# Schemat.net
KiCad netlist of a schematic drawn in EAGLE
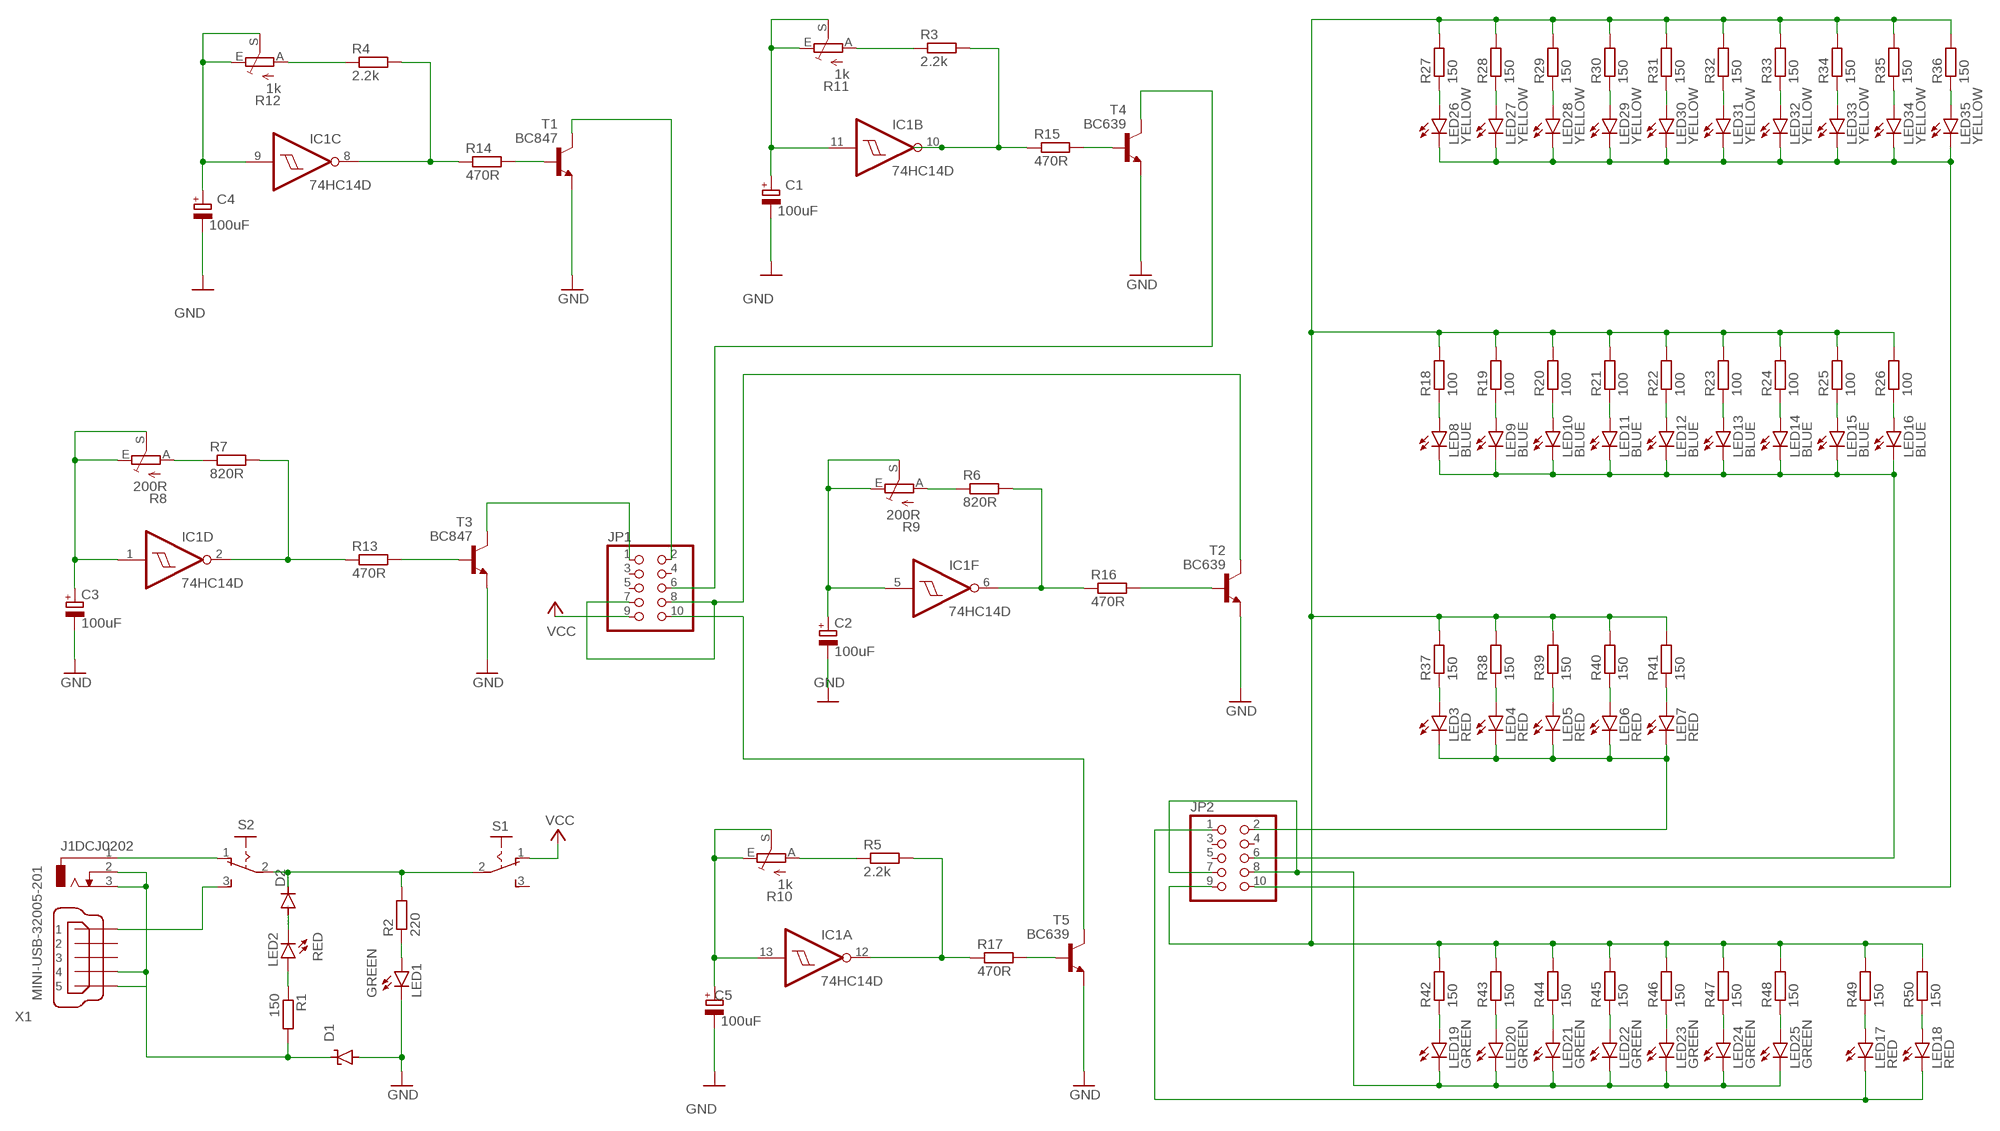
[diagram p0: schematic, sheet 1]

(export (version "E")
  (design (tool "Eeschema 10.0.6"))
  (components
    (comp (ref "C1")
      (value "100uF")
      (footprint "eagle-import:E2,5-6")
      (libsource (lib "eagle-import") (part "CPOL-EUE2.5-6"))
    )
    (comp (ref "C2")
      (value "100uF")
      (footprint "eagle-import:E2,5-6")
      (libsource (lib "eagle-import") (part "CPOL-EUE2.5-6"))
    )
    (comp (ref "C3")
      (value "100uF")
      (footprint "eagle-import:E2,5-6")
      (libsource (lib "eagle-import") (part "CPOL-EUE2.5-6"))
    )
    (comp (ref "C4")
      (value "100uF")
      (footprint "eagle-import:E2,5-6")
      (libsource (lib "eagle-import") (part "CPOL-EUE2.5-6"))
    )
    (comp (ref "C5")
      (value "100uF")
      (footprint "eagle-import:E2,5-6")
      (libsource (lib "eagle-import") (part "CPOL-EUE2.5-6"))
    )
    (comp (ref "D1")
      (value "SUPPRESSOR-SMBJ")
      (footprint "eagle-import:SMBJ")
      (libsource (lib "eagle-import") (part "SUPPRESSOR-SMBJ"))
    )
    (comp (ref "D2")
      (value "DIODE-DO214AC")
      (footprint "eagle-import:DO214AC")
      (libsource (lib "eagle-import") (part "DIODE-DO214AC"))
    )
    (comp (ref "IC1")
      (value "74HC14D")
      (footprint "eagle-import:SO14")
      (libsource (lib "eagle-import") (part "7414DHC"))
    )
    (comp (ref "J1")
      (value "DCJ0202")
      (footprint "eagle-import:DCJ0202")
      (libsource (lib "eagle-import") (part "DCJ0202"))
    )
    (comp (ref "JP1")
      (value "PINHD-2X5")
      (footprint "eagle-import:2X05")
      (libsource (lib "eagle-import") (part "PINHD-2X5"))
    )
    (comp (ref "JP2")
      (value "PINHD-2X5/90")
      (footprint "eagle-import:2X05_90")
      (libsource (lib "eagle-import") (part "PINHD-2X5/90"))
    )
    (comp (ref "LED1")
      (value "GREEN")
      (footprint "eagle-import:LED3MM")
      (libsource (lib "eagle-import") (part "LED3MM"))
    )
    (comp (ref "LED2")
      (value "RED")
      (footprint "eagle-import:LED5MM")
      (libsource (lib "eagle-import") (part "LED5MM"))
    )
    (comp (ref "LED3")
      (value "RED")
      (footprint "eagle-import:LED5MM")
      (libsource (lib "eagle-import") (part "LED5MM"))
    )
    (comp (ref "LED4")
      (value "RED")
      (footprint "eagle-import:LED5MM")
      (libsource (lib "eagle-import") (part "LED5MM"))
    )
    (comp (ref "LED5")
      (value "RED")
      (footprint "eagle-import:LED5MM")
      (libsource (lib "eagle-import") (part "LED5MM"))
    )
    (comp (ref "LED6")
      (value "RED")
      (footprint "eagle-import:LED5MM")
      (libsource (lib "eagle-import") (part "LED5MM"))
    )
    (comp (ref "LED7")
      (value "RED")
      (footprint "eagle-import:LED5MM")
      (libsource (lib "eagle-import") (part "LED5MM"))
    )
    (comp (ref "LED8")
      (value "BLUE")
      (footprint "eagle-import:LED5MM")
      (libsource (lib "eagle-import") (part "LED5MM"))
    )
    (comp (ref "LED9")
      (value "BLUE")
      (footprint "eagle-import:LED5MM")
      (libsource (lib "eagle-import") (part "LED5MM"))
    )
    (comp (ref "LED10")
      (value "BLUE")
      (footprint "eagle-import:LED5MM")
      (libsource (lib "eagle-import") (part "LED5MM"))
    )
    (comp (ref "LED11")
      (value "BLUE")
      (footprint "eagle-import:LED5MM")
      (libsource (lib "eagle-import") (part "LED5MM"))
    )
    (comp (ref "LED12")
      (value "BLUE")
      (footprint "eagle-import:LED5MM")
      (libsource (lib "eagle-import") (part "LED5MM"))
    )
    (comp (ref "LED13")
      (value "BLUE")
      (footprint "eagle-import:LED5MM")
      (libsource (lib "eagle-import") (part "LED5MM"))
    )
    (comp (ref "LED14")
      (value "BLUE")
      (footprint "eagle-import:LED5MM")
      (libsource (lib "eagle-import") (part "LED5MM"))
    )
    (comp (ref "LED15")
      (value "BLUE")
      (footprint "eagle-import:LED5MM")
      (libsource (lib "eagle-import") (part "LED5MM"))
    )
    (comp (ref "LED16")
      (value "BLUE")
      (footprint "eagle-import:LED5MM")
      (libsource (lib "eagle-import") (part "LED5MM"))
    )
    (comp (ref "LED17")
      (value "RED")
      (footprint "eagle-import:LED5MM")
      (libsource (lib "eagle-import") (part "LED5MM"))
    )
    (comp (ref "LED18")
      (value "RED")
      (footprint "eagle-import:LED5MM")
      (libsource (lib "eagle-import") (part "LED5MM"))
    )
    (comp (ref "LED19")
      (value "GREEN")
      (footprint "eagle-import:LED3MM")
      (libsource (lib "eagle-import") (part "LED3MM"))
    )
    (comp (ref "LED20")
      (value "GREEN")
      (footprint "eagle-import:LED3MM")
      (libsource (lib "eagle-import") (part "LED3MM"))
    )
    (comp (ref "LED21")
      (value "GREEN")
      (footprint "eagle-import:LED3MM")
      (libsource (lib "eagle-import") (part "LED3MM"))
    )
    (comp (ref "LED22")
      (value "GREEN")
      (footprint "eagle-import:LED3MM")
      (libsource (lib "eagle-import") (part "LED3MM"))
    )
    (comp (ref "LED23")
      (value "GREEN")
      (footprint "eagle-import:LED3MM")
      (libsource (lib "eagle-import") (part "LED3MM"))
    )
    (comp (ref "LED24")
      (value "GREEN")
      (footprint "eagle-import:LED3MM")
      (libsource (lib "eagle-import") (part "LED3MM"))
    )
    (comp (ref "LED25")
      (value "GREEN")
      (footprint "eagle-import:LED3MM")
      (libsource (lib "eagle-import") (part "LED3MM"))
    )
    (comp (ref "LED26")
      (value "YELLOW")
      (footprint "eagle-import:LED5MM")
      (libsource (lib "eagle-import") (part "LED5MM"))
    )
    (comp (ref "LED27")
      (value "YELLOW")
      (footprint "eagle-import:LED5MM")
      (libsource (lib "eagle-import") (part "LED5MM"))
    )
    (comp (ref "LED28")
      (value "YELLOW")
      (footprint "eagle-import:LED5MM")
      (libsource (lib "eagle-import") (part "LED5MM"))
    )
    (comp (ref "LED29")
      (value "YELLOW")
      (footprint "eagle-import:LED5MM")
      (libsource (lib "eagle-import") (part "LED5MM"))
    )
    (comp (ref "LED30")
      (value "YELLOW")
      (footprint "eagle-import:LED5MM")
      (libsource (lib "eagle-import") (part "LED5MM"))
    )
    (comp (ref "LED31")
      (value "YELLOW")
      (footprint "eagle-import:LED5MM")
      (libsource (lib "eagle-import") (part "LED5MM"))
    )
    (comp (ref "LED32")
      (value "YELLOW")
      (footprint "eagle-import:LED5MM")
      (libsource (lib "eagle-import") (part "LED5MM"))
    )
    (comp (ref "LED33")
      (value "YELLOW")
      (footprint "eagle-import:LED5MM")
      (libsource (lib "eagle-import") (part "LED5MM"))
    )
    (comp (ref "LED34")
      (value "YELLOW")
      (footprint "eagle-import:LED5MM")
      (libsource (lib "eagle-import") (part "LED5MM"))
    )
    (comp (ref "LED35")
      (value "YELLOW")
      (footprint "eagle-import:LED5MM")
      (libsource (lib "eagle-import") (part "LED5MM"))
    )
    (comp (ref "R1")
      (value "150")
      (footprint "eagle-import:R0805")
      (libsource (lib "eagle-import") (part "R-EU_R0805"))
    )
    (comp (ref "R2")
      (value "220")
      (footprint "eagle-import:R0805")
      (libsource (lib "eagle-import") (part "R-EU_R0805"))
    )
    (comp (ref "R3")
      (value "2.2k")
      (footprint "eagle-import:R1206")
      (libsource (lib "eagle-import") (part "R-EU_R1206"))
    )
    (comp (ref "R4")
      (value "2.2k")
      (footprint "eagle-import:R1206")
      (libsource (lib "eagle-import") (part "R-EU_R1206"))
    )
    (comp (ref "R5")
      (value "2.2k")
      (footprint "eagle-import:R1206")
      (libsource (lib "eagle-import") (part "R-EU_R1206"))
    )
    (comp (ref "R6")
      (value "820R")
      (footprint "eagle-import:R1206")
      (libsource (lib "eagle-import") (part "R-EU_R1206"))
    )
    (comp (ref "R7")
      (value "820R")
      (footprint "eagle-import:R1206")
      (libsource (lib "eagle-import") (part "R-EU_R1206"))
    )
    (comp (ref "R8")
      (value "200R")
      (footprint "eagle-import:CA6V")
      (libsource (lib "eagle-import") (part "TRIM_EU-CA6V"))
    )
    (comp (ref "R9")
      (value "200R")
      (footprint "eagle-import:CA6V")
      (libsource (lib "eagle-import") (part "TRIM_EU-CA6V"))
    )
    (comp (ref "R10")
      (value "1k")
      (footprint "eagle-import:CA6V")
      (libsource (lib "eagle-import") (part "TRIM_EU-CA6V"))
    )
    (comp (ref "R11")
      (value "1k")
      (footprint "eagle-import:CA6V")
      (libsource (lib "eagle-import") (part "TRIM_EU-CA6V"))
    )
    (comp (ref "R12")
      (value "1k")
      (footprint "eagle-import:CA6V")
      (libsource (lib "eagle-import") (part "TRIM_EU-CA6V"))
    )
    (comp (ref "R13")
      (value "470R")
      (footprint "eagle-import:R1206")
      (libsource (lib "eagle-import") (part "R-EU_R1206"))
    )
    (comp (ref "R14")
      (value "470R")
      (footprint "eagle-import:R1206")
      (libsource (lib "eagle-import") (part "R-EU_R1206"))
    )
    (comp (ref "R15")
      (value "470R")
      (footprint "eagle-import:R1206")
      (libsource (lib "eagle-import") (part "R-EU_R1206"))
    )
    (comp (ref "R16")
      (value "470R")
      (footprint "eagle-import:R1206")
      (libsource (lib "eagle-import") (part "R-EU_R1206"))
    )
    (comp (ref "R17")
      (value "470R")
      (footprint "eagle-import:R1206")
      (libsource (lib "eagle-import") (part "R-EU_R1206"))
    )
    (comp (ref "R18")
      (value "100")
      (footprint "eagle-import:R0805")
      (libsource (lib "eagle-import") (part "R-EU_R0805"))
    )
    (comp (ref "R19")
      (value "100")
      (footprint "eagle-import:R0805")
      (libsource (lib "eagle-import") (part "R-EU_R0805"))
    )
    (comp (ref "R20")
      (value "100")
      (footprint "eagle-import:R0805")
      (libsource (lib "eagle-import") (part "R-EU_R0805"))
    )
    (comp (ref "R21")
      (value "100")
      (footprint "eagle-import:R0805")
      (libsource (lib "eagle-import") (part "R-EU_R0805"))
    )
    (comp (ref "R22")
      (value "100")
      (footprint "eagle-import:R0805")
      (libsource (lib "eagle-import") (part "R-EU_R0805"))
    )
    (comp (ref "R23")
      (value "100")
      (footprint "eagle-import:R0805")
      (libsource (lib "eagle-import") (part "R-EU_R0805"))
    )
    (comp (ref "R24")
      (value "100")
      (footprint "eagle-import:R0805")
      (libsource (lib "eagle-import") (part "R-EU_R0805"))
    )
    (comp (ref "R25")
      (value "100")
      (footprint "eagle-import:R0805")
      (libsource (lib "eagle-import") (part "R-EU_R0805"))
    )
    (comp (ref "R26")
      (value "100")
      (footprint "eagle-import:R0805")
      (libsource (lib "eagle-import") (part "R-EU_R0805"))
    )
    (comp (ref "R27")
      (value "150")
      (footprint "eagle-import:R0805")
      (libsource (lib "eagle-import") (part "R-EU_R0805"))
    )
    (comp (ref "R28")
      (value "150")
      (footprint "eagle-import:R0805")
      (libsource (lib "eagle-import") (part "R-EU_R0805"))
    )
    (comp (ref "R29")
      (value "150")
      (footprint "eagle-import:R0805")
      (libsource (lib "eagle-import") (part "R-EU_R0805"))
    )
    (comp (ref "R30")
      (value "150")
      (footprint "eagle-import:R0805")
      (libsource (lib "eagle-import") (part "R-EU_R0805"))
    )
    (comp (ref "R31")
      (value "150")
      (footprint "eagle-import:R0805")
      (libsource (lib "eagle-import") (part "R-EU_R0805"))
    )
    (comp (ref "R32")
      (value "150")
      (footprint "eagle-import:R0805")
      (libsource (lib "eagle-import") (part "R-EU_R0805"))
    )
    (comp (ref "R33")
      (value "150")
      (footprint "eagle-import:R0805")
      (libsource (lib "eagle-import") (part "R-EU_R0805"))
    )
    (comp (ref "R34")
      (value "150")
      (footprint "eagle-import:R0805")
      (libsource (lib "eagle-import") (part "R-EU_R0805"))
    )
    (comp (ref "R35")
      (value "150")
      (footprint "eagle-import:R0805")
      (libsource (lib "eagle-import") (part "R-EU_R0805"))
    )
    (comp (ref "R36")
      (value "150")
      (footprint "eagle-import:R0805")
      (libsource (lib "eagle-import") (part "R-EU_R0805"))
    )
    (comp (ref "R37")
      (value "150")
      (footprint "eagle-import:R0805")
      (libsource (lib "eagle-import") (part "R-EU_R0805"))
    )
    (comp (ref "R38")
      (value "150")
      (footprint "eagle-import:R0805")
      (libsource (lib "eagle-import") (part "R-EU_R0805"))
    )
    (comp (ref "R39")
      (value "150")
      (footprint "eagle-import:R0805")
      (libsource (lib "eagle-import") (part "R-EU_R0805"))
    )
    (comp (ref "R40")
      (value "150")
      (footprint "eagle-import:R0805")
      (libsource (lib "eagle-import") (part "R-EU_R0805"))
    )
    (comp (ref "R41")
      (value "150")
      (footprint "eagle-import:R0805")
      (libsource (lib "eagle-import") (part "R-EU_R0805"))
    )
    (comp (ref "R42")
      (value "150")
      (footprint "eagle-import:R0805")
      (libsource (lib "eagle-import") (part "R-EU_R0805"))
    )
    (comp (ref "R43")
      (value "150")
      (footprint "eagle-import:R0805")
      (libsource (lib "eagle-import") (part "R-EU_R0805"))
    )
    (comp (ref "R44")
      (value "150")
      (footprint "eagle-import:R0805")
      (libsource (lib "eagle-import") (part "R-EU_R0805"))
    )
    (comp (ref "R45")
      (value "150")
      (footprint "eagle-import:R0805")
      (libsource (lib "eagle-import") (part "R-EU_R0805"))
    )
    (comp (ref "R46")
      (value "150")
      (footprint "eagle-import:R0805")
      (libsource (lib "eagle-import") (part "R-EU_R0805"))
    )
    (comp (ref "R47")
      (value "150")
      (footprint "eagle-import:R0805")
      (libsource (lib "eagle-import") (part "R-EU_R0805"))
    )
    (comp (ref "R48")
      (value "150")
      (footprint "eagle-import:R0805")
      (libsource (lib "eagle-import") (part "R-EU_R0805"))
    )
    (comp (ref "R49")
      (value "150")
      (footprint "eagle-import:R0805")
      (libsource (lib "eagle-import") (part "R-EU_R0805"))
    )
    (comp (ref "R50")
      (value "150")
      (footprint "eagle-import:R0805")
      (libsource (lib "eagle-import") (part "R-EU_R0805"))
    )
    (comp (ref "S1")
      (value "M251")
      (footprint "eagle-import:M251")
      (libsource (lib "eagle-import") (part "M251"))
    )
    (comp (ref "S2")
      (value "M251")
      (footprint "eagle-import:M251")
      (libsource (lib "eagle-import") (part "M251"))
    )
    (comp (ref "T1")
      (value "BC847")
      (footprint "eagle-import:SOT23")
      (libsource (lib "eagle-import") (part "BC847"))
    )
    (comp (ref "T2")
      (value "BC639")
      (footprint "eagle-import:TO92-ECB")
      (libsource (lib "eagle-import") (part "-NPN-TO92-ECBBC639"))
    )
    (comp (ref "T3")
      (value "BC847")
      (footprint "eagle-import:SOT23")
      (libsource (lib "eagle-import") (part "BC847"))
    )
    (comp (ref "T4")
      (value "BC639")
      (footprint "eagle-import:TO92-ECB")
      (libsource (lib "eagle-import") (part "-NPN-TO92-ECBBC639"))
    )
    (comp (ref "T5")
      (value "BC639")
      (footprint "eagle-import:TO92-ECB")
      (libsource (lib "eagle-import") (part "-NPN-TO92-ECBBC639"))
    )
    (comp (ref "X1")
      (value "MINI-USB-32005-201")
      (footprint "eagle-import:32005-201")
      (libsource (lib "eagle-import") (part "MINI-USB-32005-201"))
    )
  )
  (nets
    (net (code "1") (name "GND") (class "Default")
      (node (ref "C1") (pin "-") (pinfunction "-_-") (pintype "passive"))
      (node (ref "C2") (pin "-") (pinfunction "-_-") (pintype "passive"))
      (node (ref "C3") (pin "-") (pinfunction "-_-") (pintype "passive"))
      (node (ref "C4") (pin "-") (pinfunction "-_-") (pintype "passive"))
      (node (ref "C5") (pin "-") (pinfunction "-_-") (pintype "passive"))
      (node (ref "D1") (pin "A") (pinfunction "A_A") (pintype "passive"))
      (node (ref "LED1") (pin "K") (pinfunction "C_K") (pintype "passive"))
      (node (ref "T1") (pin "2") (pinfunction "E_2") (pintype "passive"))
      (node (ref "T2") (pin "E") (pinfunction "E_E") (pintype "passive"))
      (node (ref "T3") (pin "2") (pinfunction "E_2") (pintype "passive"))
      (node (ref "T4") (pin "E") (pinfunction "E_E") (pintype "passive"))
      (node (ref "T5") (pin "E") (pinfunction "E_E") (pintype "passive"))
    )
    (net (code "2") (name "Net-(D1-PadC)") (class "Default")
      (node (ref "D1") (pin "C") (pinfunction "C_C") (pintype "passive"))
      (node (ref "J1") (pin "2") (pinfunction "2_2") (pintype "passive"))
      (node (ref "J1") (pin "3") (pinfunction "3_3") (pintype "passive"))
      (node (ref "R1") (pin "2") (pinfunction "2_2") (pintype "passive"))
      (node (ref "X1") (pin "4") (pinfunction "4_4") (pintype "passive"))
      (node (ref "X1") (pin "5") (pinfunction "5_5") (pintype "passive"))
    )
    (net (code "3") (name "Net-(IC1A-I)") (class "Default")
      (node (ref "C5") (pin "+") (pinfunction "+_+") (pintype "passive"))
      (node (ref "IC1") (pin "13") (pinfunction "I_13") (pintype "input"))
      (node (ref "R10") (pin "E") (pinfunction "E_E") (pintype "passive"))
      (node (ref "R10") (pin "S") (pinfunction "S_S") (pintype "passive"))
    )
    (net (code "4") (name "Net-(IC1A-O)") (class "Default")
      (node (ref "IC1") (pin "12") (pinfunction "O_12") (pintype "output"))
      (node (ref "R17") (pin "1") (pinfunction "1_1") (pintype "passive"))
      (node (ref "R5") (pin "2") (pinfunction "2_2") (pintype "passive"))
    )
    (net (code "5") (name "Net-(IC1B-I)") (class "Default")
      (node (ref "C1") (pin "+") (pinfunction "+_+") (pintype "passive"))
      (node (ref "IC1") (pin "11") (pinfunction "I_11") (pintype "input"))
      (node (ref "R11") (pin "E") (pinfunction "E_E") (pintype "passive"))
      (node (ref "R11") (pin "S") (pinfunction "S_S") (pintype "passive"))
    )
    (net (code "6") (name "Net-(IC1B-O)") (class "Default")
      (node (ref "IC1") (pin "10") (pinfunction "O_10") (pintype "output"))
      (node (ref "R15") (pin "1") (pinfunction "1_1") (pintype "passive"))
      (node (ref "R3") (pin "2") (pinfunction "2_2") (pintype "passive"))
    )
    (net (code "7") (name "Net-(IC1C-I)") (class "Default")
      (node (ref "C4") (pin "+") (pinfunction "+_+") (pintype "passive"))
      (node (ref "IC1") (pin "9") (pinfunction "I_9") (pintype "input"))
      (node (ref "R12") (pin "E") (pinfunction "E_E") (pintype "passive"))
      (node (ref "R12") (pin "S") (pinfunction "S_S") (pintype "passive"))
    )
    (net (code "8") (name "Net-(IC1C-O)") (class "Default")
      (node (ref "IC1") (pin "8") (pinfunction "O_8") (pintype "output"))
      (node (ref "R14") (pin "1") (pinfunction "1_1") (pintype "passive"))
      (node (ref "R4") (pin "2") (pinfunction "2_2") (pintype "passive"))
    )
    (net (code "9") (name "Net-(IC1D-I)") (class "Default")
      (node (ref "C3") (pin "+") (pinfunction "+_+") (pintype "passive"))
      (node (ref "IC1") (pin "1") (pinfunction "I_1") (pintype "input"))
      (node (ref "R8") (pin "E") (pinfunction "E_E") (pintype "passive"))
      (node (ref "R8") (pin "S") (pinfunction "S_S") (pintype "passive"))
    )
    (net (code "10") (name "Net-(IC1D-O)") (class "Default")
      (node (ref "IC1") (pin "2") (pinfunction "O_2") (pintype "output"))
      (node (ref "R13") (pin "1") (pinfunction "1_1") (pintype "passive"))
      (node (ref "R7") (pin "2") (pinfunction "2_2") (pintype "passive"))
    )
    (net (code "11") (name "Net-(IC1F-I)") (class "Default")
      (node (ref "C2") (pin "+") (pinfunction "+_+") (pintype "passive"))
      (node (ref "IC1") (pin "5") (pinfunction "I_5") (pintype "input"))
      (node (ref "R9") (pin "E") (pinfunction "E_E") (pintype "passive"))
      (node (ref "R9") (pin "S") (pinfunction "S_S") (pintype "passive"))
    )
    (net (code "12") (name "Net-(IC1F-O)") (class "Default")
      (node (ref "IC1") (pin "6") (pinfunction "O_6") (pintype "output"))
      (node (ref "R16") (pin "1") (pinfunction "1_1") (pintype "passive"))
      (node (ref "R6") (pin "2") (pinfunction "2_2") (pintype "passive"))
    )
    (net (code "13") (name "Net-(JP1-Pad6)") (class "Default")
      (node (ref "JP1") (pin "6") (pinfunction "6_6") (pintype "passive"))
      (node (ref "T4") (pin "C") (pinfunction "C_C") (pintype "passive"))
    )
    (net (code "14") (name "Net-(JP1-Pad7)") (class "Default")
      (node (ref "JP1") (pin "7") (pinfunction "7_7") (pintype "passive"))
      (node (ref "JP1") (pin "8") (pinfunction "8_8") (pintype "passive"))
      (node (ref "T2") (pin "C") (pinfunction "C_C") (pintype "passive"))
    )
    (net (code "15") (name "Net-(JP1-Pad10)") (class "Default")
      (node (ref "JP1") (pin "10") (pinfunction "10_10") (pintype "passive"))
      (node (ref "T5") (pin "C") (pinfunction "C_C") (pintype "passive"))
    )
    (net (code "16") (name "Net-(JP2-Pad9)") (class "Default")
      (node (ref "JP2") (pin "9") (pinfunction "9_9") (pintype "passive"))
      (node (ref "R18") (pin "2") (pinfunction "2_2") (pintype "passive"))
      (node (ref "R19") (pin "2") (pinfunction "2_2") (pintype "passive"))
      (node (ref "R20") (pin "2") (pinfunction "2_2") (pintype "passive"))
      (node (ref "R21") (pin "2") (pinfunction "2_2") (pintype "passive"))
      (node (ref "R22") (pin "2") (pinfunction "2_2") (pintype "passive"))
      (node (ref "R23") (pin "2") (pinfunction "2_2") (pintype "passive"))
      (node (ref "R24") (pin "2") (pinfunction "2_2") (pintype "passive"))
      (node (ref "R25") (pin "2") (pinfunction "2_2") (pintype "passive"))
      (node (ref "R26") (pin "2") (pinfunction "2_2") (pintype "passive"))
      (node (ref "R27") (pin "2") (pinfunction "2_2") (pintype "passive"))
      (node (ref "R28") (pin "2") (pinfunction "2_2") (pintype "passive"))
      (node (ref "R29") (pin "2") (pinfunction "2_2") (pintype "passive"))
      (node (ref "R30") (pin "2") (pinfunction "2_2") (pintype "passive"))
      (node (ref "R31") (pin "2") (pinfunction "2_2") (pintype "passive"))
      (node (ref "R32") (pin "2") (pinfunction "2_2") (pintype "passive"))
      (node (ref "R33") (pin "2") (pinfunction "2_2") (pintype "passive"))
      (node (ref "R34") (pin "2") (pinfunction "2_2") (pintype "passive"))
      (node (ref "R35") (pin "2") (pinfunction "2_2") (pintype "passive"))
      (node (ref "R36") (pin "2") (pinfunction "2_2") (pintype "passive"))
      (node (ref "R37") (pin "2") (pinfunction "2_2") (pintype "passive"))
      (node (ref "R38") (pin "2") (pinfunction "2_2") (pintype "passive"))
      (node (ref "R39") (pin "2") (pinfunction "2_2") (pintype "passive"))
      (node (ref "R40") (pin "2") (pinfunction "2_2") (pintype "passive"))
      (node (ref "R41") (pin "2") (pinfunction "2_2") (pintype "passive"))
      (node (ref "R42") (pin "2") (pinfunction "2_2") (pintype "passive"))
      (node (ref "R43") (pin "2") (pinfunction "2_2") (pintype "passive"))
      (node (ref "R44") (pin "2") (pinfunction "2_2") (pintype "passive"))
      (node (ref "R45") (pin "2") (pinfunction "2_2") (pintype "passive"))
      (node (ref "R46") (pin "2") (pinfunction "2_2") (pintype "passive"))
      (node (ref "R47") (pin "2") (pinfunction "2_2") (pintype "passive"))
      (node (ref "R48") (pin "2") (pinfunction "2_2") (pintype "passive"))
      (node (ref "R49") (pin "2") (pinfunction "2_2") (pintype "passive"))
      (node (ref "R50") (pin "2") (pinfunction "2_2") (pintype "passive"))
    )
    (net (code "17") (name "Net-(LED1-PadA)") (class "Default")
      (node (ref "LED1") (pin "A") (pinfunction "A_A") (pintype "passive"))
      (node (ref "R2") (pin "1") (pinfunction "1_1") (pintype "passive"))
    )
    (net (code "18") (name "Net-(LED2-C)") (class "Default")
      (node (ref "D2") (pin "A") (pinfunction "A_A") (pintype "passive"))
      (node (ref "LED2") (pin "K") (pinfunction "C_K") (pintype "passive"))
    )
    (net (code "19") (name "Net-(LED2-PadA)") (class "Default")
      (node (ref "LED2") (pin "A") (pinfunction "A_A") (pintype "passive"))
      (node (ref "R1") (pin "1") (pinfunction "1_1") (pintype "passive"))
    )
    (net (code "20") (name "Net-(LED3-C)") (class "Default")
      (node (ref "JP2") (pin "2") (pinfunction "2_2") (pintype "passive"))
      (node (ref "LED3") (pin "K") (pinfunction "C_K") (pintype "passive"))
      (node (ref "LED4") (pin "K") (pinfunction "C_K") (pintype "passive"))
      (node (ref "LED5") (pin "K") (pinfunction "C_K") (pintype "passive"))
      (node (ref "LED6") (pin "K") (pinfunction "C_K") (pintype "passive"))
      (node (ref "LED7") (pin "K") (pinfunction "C_K") (pintype "passive"))
    )
    (net (code "21") (name "Net-(LED3-PadA)") (class "Default")
      (node (ref "LED3") (pin "A") (pinfunction "A_A") (pintype "passive"))
      (node (ref "R37") (pin "1") (pinfunction "1_1") (pintype "passive"))
    )
    (net (code "22") (name "Net-(LED4-PadA)") (class "Default")
      (node (ref "LED4") (pin "A") (pinfunction "A_A") (pintype "passive"))
      (node (ref "R38") (pin "1") (pinfunction "1_1") (pintype "passive"))
    )
    (net (code "23") (name "Net-(LED5-PadA)") (class "Default")
      (node (ref "LED5") (pin "A") (pinfunction "A_A") (pintype "passive"))
      (node (ref "R39") (pin "1") (pinfunction "1_1") (pintype "passive"))
    )
    (net (code "24") (name "Net-(LED6-PadA)") (class "Default")
      (node (ref "LED6") (pin "A") (pinfunction "A_A") (pintype "passive"))
      (node (ref "R40") (pin "1") (pinfunction "1_1") (pintype "passive"))
    )
    (net (code "25") (name "Net-(LED7-PadA)") (class "Default")
      (node (ref "LED7") (pin "A") (pinfunction "A_A") (pintype "passive"))
      (node (ref "R41") (pin "1") (pinfunction "1_1") (pintype "passive"))
    )
    (net (code "26") (name "Net-(LED8-PadA)") (class "Default")
      (node (ref "LED8") (pin "A") (pinfunction "A_A") (pintype "passive"))
      (node (ref "R18") (pin "1") (pinfunction "1_1") (pintype "passive"))
    )
    (net (code "27") (name "Net-(LED9-PadA)") (class "Default")
      (node (ref "LED9") (pin "A") (pinfunction "A_A") (pintype "passive"))
      (node (ref "R19") (pin "1") (pinfunction "1_1") (pintype "passive"))
    )
    (net (code "28") (name "Net-(LED10-C)") (class "Default")
      (node (ref "JP2") (pin "6") (pinfunction "6_6") (pintype "passive"))
      (node (ref "LED10") (pin "K") (pinfunction "C_K") (pintype "passive"))
      (node (ref "LED11") (pin "K") (pinfunction "C_K") (pintype "passive"))
      (node (ref "LED12") (pin "K") (pinfunction "C_K") (pintype "passive"))
      (node (ref "LED13") (pin "K") (pinfunction "C_K") (pintype "passive"))
      (node (ref "LED14") (pin "K") (pinfunction "C_K") (pintype "passive"))
      (node (ref "LED15") (pin "K") (pinfunction "C_K") (pintype "passive"))
      (node (ref "LED16") (pin "K") (pinfunction "C_K") (pintype "passive"))
      (node (ref "LED8") (pin "K") (pinfunction "C_K") (pintype "passive"))
      (node (ref "LED9") (pin "K") (pinfunction "C_K") (pintype "passive"))
    )
    (net (code "29") (name "Net-(LED10-PadA)") (class "Default")
      (node (ref "LED10") (pin "A") (pinfunction "A_A") (pintype "passive"))
      (node (ref "R20") (pin "1") (pinfunction "1_1") (pintype "passive"))
    )
    (net (code "30") (name "Net-(LED11-PadA)") (class "Default")
      (node (ref "LED11") (pin "A") (pinfunction "A_A") (pintype "passive"))
      (node (ref "R21") (pin "1") (pinfunction "1_1") (pintype "passive"))
    )
    (net (code "31") (name "Net-(LED12-PadA)") (class "Default")
      (node (ref "LED12") (pin "A") (pinfunction "A_A") (pintype "passive"))
      (node (ref "R22") (pin "1") (pinfunction "1_1") (pintype "passive"))
    )
    (net (code "32") (name "Net-(LED13-PadA)") (class "Default")
      (node (ref "LED13") (pin "A") (pinfunction "A_A") (pintype "passive"))
      (node (ref "R23") (pin "1") (pinfunction "1_1") (pintype "passive"))
    )
    (net (code "33") (name "Net-(LED14-PadA)") (class "Default")
      (node (ref "LED14") (pin "A") (pinfunction "A_A") (pintype "passive"))
      (node (ref "R24") (pin "1") (pinfunction "1_1") (pintype "passive"))
    )
    (net (code "34") (name "Net-(LED15-PadA)") (class "Default")
      (node (ref "LED15") (pin "A") (pinfunction "A_A") (pintype "passive"))
      (node (ref "R25") (pin "1") (pinfunction "1_1") (pintype "passive"))
    )
    (net (code "35") (name "Net-(LED16-PadA)") (class "Default")
      (node (ref "LED16") (pin "A") (pinfunction "A_A") (pintype "passive"))
      (node (ref "R26") (pin "1") (pinfunction "1_1") (pintype "passive"))
    )
    (net (code "36") (name "Net-(LED17-C)") (class "Default")
      (node (ref "JP2") (pin "1") (pinfunction "1_1") (pintype "passive"))
      (node (ref "LED17") (pin "K") (pinfunction "C_K") (pintype "passive"))
      (node (ref "LED18") (pin "K") (pinfunction "C_K") (pintype "passive"))
    )
    (net (code "37") (name "Net-(LED17-PadA)") (class "Default")
      (node (ref "LED17") (pin "A") (pinfunction "A_A") (pintype "passive"))
      (node (ref "R49") (pin "1") (pinfunction "1_1") (pintype "passive"))
    )
    (net (code "38") (name "Net-(LED18-PadA)") (class "Default")
      (node (ref "LED18") (pin "A") (pinfunction "A_A") (pintype "passive"))
      (node (ref "R50") (pin "1") (pinfunction "1_1") (pintype "passive"))
    )
    (net (code "39") (name "Net-(LED19-C)") (class "Default")
      (node (ref "JP2") (pin "7") (pinfunction "7_7") (pintype "passive"))
      (node (ref "JP2") (pin "8") (pinfunction "8_8") (pintype "passive"))
      (node (ref "LED19") (pin "K") (pinfunction "C_K") (pintype "passive"))
      (node (ref "LED20") (pin "K") (pinfunction "C_K") (pintype "passive"))
      (node (ref "LED21") (pin "K") (pinfunction "C_K") (pintype "passive"))
      (node (ref "LED22") (pin "K") (pinfunction "C_K") (pintype "passive"))
      (node (ref "LED23") (pin "K") (pinfunction "C_K") (pintype "passive"))
      (node (ref "LED24") (pin "K") (pinfunction "C_K") (pintype "passive"))
      (node (ref "LED25") (pin "K") (pinfunction "C_K") (pintype "passive"))
    )
    (net (code "40") (name "Net-(LED19-PadA)") (class "Default")
      (node (ref "LED19") (pin "A") (pinfunction "A_A") (pintype "passive"))
      (node (ref "R42") (pin "1") (pinfunction "1_1") (pintype "passive"))
    )
    (net (code "41") (name "Net-(LED20-PadA)") (class "Default")
      (node (ref "LED20") (pin "A") (pinfunction "A_A") (pintype "passive"))
      (node (ref "R43") (pin "1") (pinfunction "1_1") (pintype "passive"))
    )
    (net (code "42") (name "Net-(LED21-PadA)") (class "Default")
      (node (ref "LED21") (pin "A") (pinfunction "A_A") (pintype "passive"))
      (node (ref "R44") (pin "1") (pinfunction "1_1") (pintype "passive"))
    )
    (net (code "43") (name "Net-(LED22-PadA)") (class "Default")
      (node (ref "LED22") (pin "A") (pinfunction "A_A") (pintype "passive"))
      (node (ref "R45") (pin "1") (pinfunction "1_1") (pintype "passive"))
    )
    (net (code "44") (name "Net-(LED23-PadA)") (class "Default")
      (node (ref "LED23") (pin "A") (pinfunction "A_A") (pintype "passive"))
      (node (ref "R46") (pin "1") (pinfunction "1_1") (pintype "passive"))
    )
    (net (code "45") (name "Net-(LED24-PadA)") (class "Default")
      (node (ref "LED24") (pin "A") (pinfunction "A_A") (pintype "passive"))
      (node (ref "R47") (pin "1") (pinfunction "1_1") (pintype "passive"))
    )
    (net (code "46") (name "Net-(LED25-PadA)") (class "Default")
      (node (ref "LED25") (pin "A") (pinfunction "A_A") (pintype "passive"))
      (node (ref "R48") (pin "1") (pinfunction "1_1") (pintype "passive"))
    )
    (net (code "47") (name "Net-(LED26-C)") (class "Default")
      (node (ref "JP2") (pin "10") (pinfunction "10_10") (pintype "passive"))
      (node (ref "LED26") (pin "K") (pinfunction "C_K") (pintype "passive"))
      (node (ref "LED27") (pin "K") (pinfunction "C_K") (pintype "passive"))
      (node (ref "LED28") (pin "K") (pinfunction "C_K") (pintype "passive"))
      (node (ref "LED29") (pin "K") (pinfunction "C_K") (pintype "passive"))
      (node (ref "LED30") (pin "K") (pinfunction "C_K") (pintype "passive"))
      (node (ref "LED31") (pin "K") (pinfunction "C_K") (pintype "passive"))
      (node (ref "LED32") (pin "K") (pinfunction "C_K") (pintype "passive"))
      (node (ref "LED33") (pin "K") (pinfunction "C_K") (pintype "passive"))
      (node (ref "LED34") (pin "K") (pinfunction "C_K") (pintype "passive"))
      (node (ref "LED35") (pin "K") (pinfunction "C_K") (pintype "passive"))
    )
    (net (code "48") (name "Net-(LED26-PadA)") (class "Default")
      (node (ref "LED26") (pin "A") (pinfunction "A_A") (pintype "passive"))
      (node (ref "R27") (pin "1") (pinfunction "1_1") (pintype "passive"))
    )
    (net (code "49") (name "Net-(LED27-PadA)") (class "Default")
      (node (ref "LED27") (pin "A") (pinfunction "A_A") (pintype "passive"))
      (node (ref "R28") (pin "1") (pinfunction "1_1") (pintype "passive"))
    )
    (net (code "50") (name "Net-(LED28-PadA)") (class "Default")
      (node (ref "LED28") (pin "A") (pinfunction "A_A") (pintype "passive"))
      (node (ref "R29") (pin "1") (pinfunction "1_1") (pintype "passive"))
    )
    (net (code "51") (name "Net-(LED29-PadA)") (class "Default")
      (node (ref "LED29") (pin "A") (pinfunction "A_A") (pintype "passive"))
      (node (ref "R30") (pin "1") (pinfunction "1_1") (pintype "passive"))
    )
    (net (code "52") (name "Net-(LED30-PadA)") (class "Default")
      (node (ref "LED30") (pin "A") (pinfunction "A_A") (pintype "passive"))
      (node (ref "R31") (pin "1") (pinfunction "1_1") (pintype "passive"))
    )
    (net (code "53") (name "Net-(LED31-PadA)") (class "Default")
      (node (ref "LED31") (pin "A") (pinfunction "A_A") (pintype "passive"))
      (node (ref "R32") (pin "1") (pinfunction "1_1") (pintype "passive"))
    )
    (net (code "54") (name "Net-(LED32-PadA)") (class "Default")
      (node (ref "LED32") (pin "A") (pinfunction "A_A") (pintype "passive"))
      (node (ref "R33") (pin "1") (pinfunction "1_1") (pintype "passive"))
    )
    (net (code "55") (name "Net-(LED33-PadA)") (class "Default")
      (node (ref "LED33") (pin "A") (pinfunction "A_A") (pintype "passive"))
      (node (ref "R34") (pin "1") (pinfunction "1_1") (pintype "passive"))
    )
    (net (code "56") (name "Net-(LED34-PadA)") (class "Default")
      (node (ref "LED34") (pin "A") (pinfunction "A_A") (pintype "passive"))
      (node (ref "R35") (pin "1") (pinfunction "1_1") (pintype "passive"))
    )
    (net (code "57") (name "Net-(LED35-PadA)") (class "Default")
      (node (ref "LED35") (pin "A") (pinfunction "A_A") (pintype "passive"))
      (node (ref "R36") (pin "1") (pinfunction "1_1") (pintype "passive"))
    )
    (net (code "58") (name "Net-(R6-Pad1)") (class "Default")
      (node (ref "R6") (pin "1") (pinfunction "1_1") (pintype "passive"))
      (node (ref "R9") (pin "A") (pinfunction "A_A") (pintype "passive"))
    )
    (net (code "59") (name "Net-(R7-Pad1)") (class "Default")
      (node (ref "R7") (pin "1") (pinfunction "1_1") (pintype "passive"))
      (node (ref "R8") (pin "A") (pinfunction "A_A") (pintype "passive"))
    )
    (net (code "60") (name "Net-(R10-PadA)") (class "Default")
      (node (ref "R10") (pin "A") (pinfunction "A_A") (pintype "passive"))
      (node (ref "R5") (pin "1") (pinfunction "1_1") (pintype "passive"))
    )
    (net (code "61") (name "Net-(R11-PadA)") (class "Default")
      (node (ref "R11") (pin "A") (pinfunction "A_A") (pintype "passive"))
      (node (ref "R3") (pin "1") (pinfunction "1_1") (pintype "passive"))
    )
    (net (code "62") (name "Net-(R12-PadA)") (class "Default")
      (node (ref "R12") (pin "A") (pinfunction "A_A") (pintype "passive"))
      (node (ref "R4") (pin "1") (pinfunction "1_1") (pintype "passive"))
    )
    (net (code "63") (name "Net-(R15-Pad2)") (class "Default")
      (node (ref "R15") (pin "2") (pinfunction "2_2") (pintype "passive"))
      (node (ref "T4") (pin "B") (pinfunction "B_B") (pintype "passive"))
    )
    (net (code "64") (name "Net-(R16-Pad2)") (class "Default")
      (node (ref "R16") (pin "2") (pinfunction "2_2") (pintype "passive"))
      (node (ref "T2") (pin "B") (pinfunction "B_B") (pintype "passive"))
    )
    (net (code "65") (name "Net-(R17-Pad2)") (class "Default")
      (node (ref "R17") (pin "2") (pinfunction "2_2") (pintype "passive"))
      (node (ref "T5") (pin "B") (pinfunction "B_B") (pintype "passive"))
    )
    (net (code "66") (name "Net-(S1-P)") (class "Default")
      (node (ref "D2") (pin "C") (pinfunction "C_C") (pintype "passive"))
      (node (ref "R2") (pin "2") (pinfunction "2_2") (pintype "passive"))
      (node (ref "S1") (pin "2") (pinfunction "P_2") (pintype "passive"))
      (node (ref "S2") (pin "2") (pinfunction "P_2") (pintype "passive"))
    )
    (net (code "67") (name "Net-(S2-O)") (class "Default")
      (node (ref "J1") (pin "1") (pinfunction "1_1") (pintype "passive"))
      (node (ref "S2") (pin "1") (pinfunction "O_1") (pintype "passive"))
    )
    (net (code "68") (name "Net-(S2-S)") (class "Default")
      (node (ref "S2") (pin "3") (pinfunction "S_3") (pintype "passive"))
      (node (ref "X1") (pin "1") (pinfunction "1_1") (pintype "passive"))
    )
    (net (code "69") (name "Net-(T1-B)") (class "Default")
      (node (ref "R14") (pin "2") (pinfunction "2_2") (pintype "passive"))
      (node (ref "T1") (pin "1") (pinfunction "B_1") (pintype "passive"))
    )
    (net (code "70") (name "Net-(T1-C)") (class "Default")
      (node (ref "JP1") (pin "2") (pinfunction "2_2") (pintype "passive"))
      (node (ref "T1") (pin "3") (pinfunction "C_3") (pintype "passive"))
    )
    (net (code "71") (name "Net-(T3-B)") (class "Default")
      (node (ref "R13") (pin "2") (pinfunction "2_2") (pintype "passive"))
      (node (ref "T3") (pin "1") (pinfunction "B_1") (pintype "passive"))
    )
    (net (code "72") (name "Net-(T3-C)") (class "Default")
      (node (ref "JP1") (pin "1") (pinfunction "1_1") (pintype "passive"))
      (node (ref "T3") (pin "3") (pinfunction "C_3") (pintype "passive"))
    )
    (net (code "73") (name "VCC") (class "Default")
      (node (ref "JP1") (pin "9") (pinfunction "9_9") (pintype "passive"))
      (node (ref "S1") (pin "1") (pinfunction "O_1") (pintype "passive"))
    )
    (net (code "74") (name "unconnected-(JP1-Pad3)") (class "Default")
      (node (ref "JP1") (pin "3") (pinfunction "3_3") (pintype "passive"))
    )
    (net (code "75") (name "unconnected-(JP1-Pad4)") (class "Default")
      (node (ref "JP1") (pin "4") (pinfunction "4_4") (pintype "passive"))
    )
    (net (code "76") (name "unconnected-(JP1-Pad5)") (class "Default")
      (node (ref "JP1") (pin "5") (pinfunction "5_5") (pintype "passive"))
    )
    (net (code "77") (name "unconnected-(JP2-Pad3)") (class "Default")
      (node (ref "JP2") (pin "3") (pinfunction "3_3") (pintype "passive"))
    )
    (net (code "78") (name "unconnected-(JP2-Pad4)") (class "Default")
      (node (ref "JP2") (pin "4") (pinfunction "4_4") (pintype "passive"))
    )
    (net (code "79") (name "unconnected-(JP2-Pad5)") (class "Default")
      (node (ref "JP2") (pin "5") (pinfunction "5_5") (pintype "passive"))
    )
    (net (code "80") (name "unconnected-(S1-S-Pad3)") (class "Default")
      (node (ref "S1") (pin "3") (pinfunction "S_3") (pintype "passive"))
    )
    (net (code "81") (name "unconnected-(X1-Pad2)") (class "Default")
      (node (ref "X1") (pin "2") (pinfunction "2_2") (pintype "passive"))
    )
    (net (code "82") (name "unconnected-(X1-Pad3)") (class "Default")
      (node (ref "X1") (pin "3") (pinfunction "3_3") (pintype "passive"))
    )
  )
)
